# CC2530-CP2102-USB-V01-014.net
KiCad netlist of a schematic drawn in EAGLE
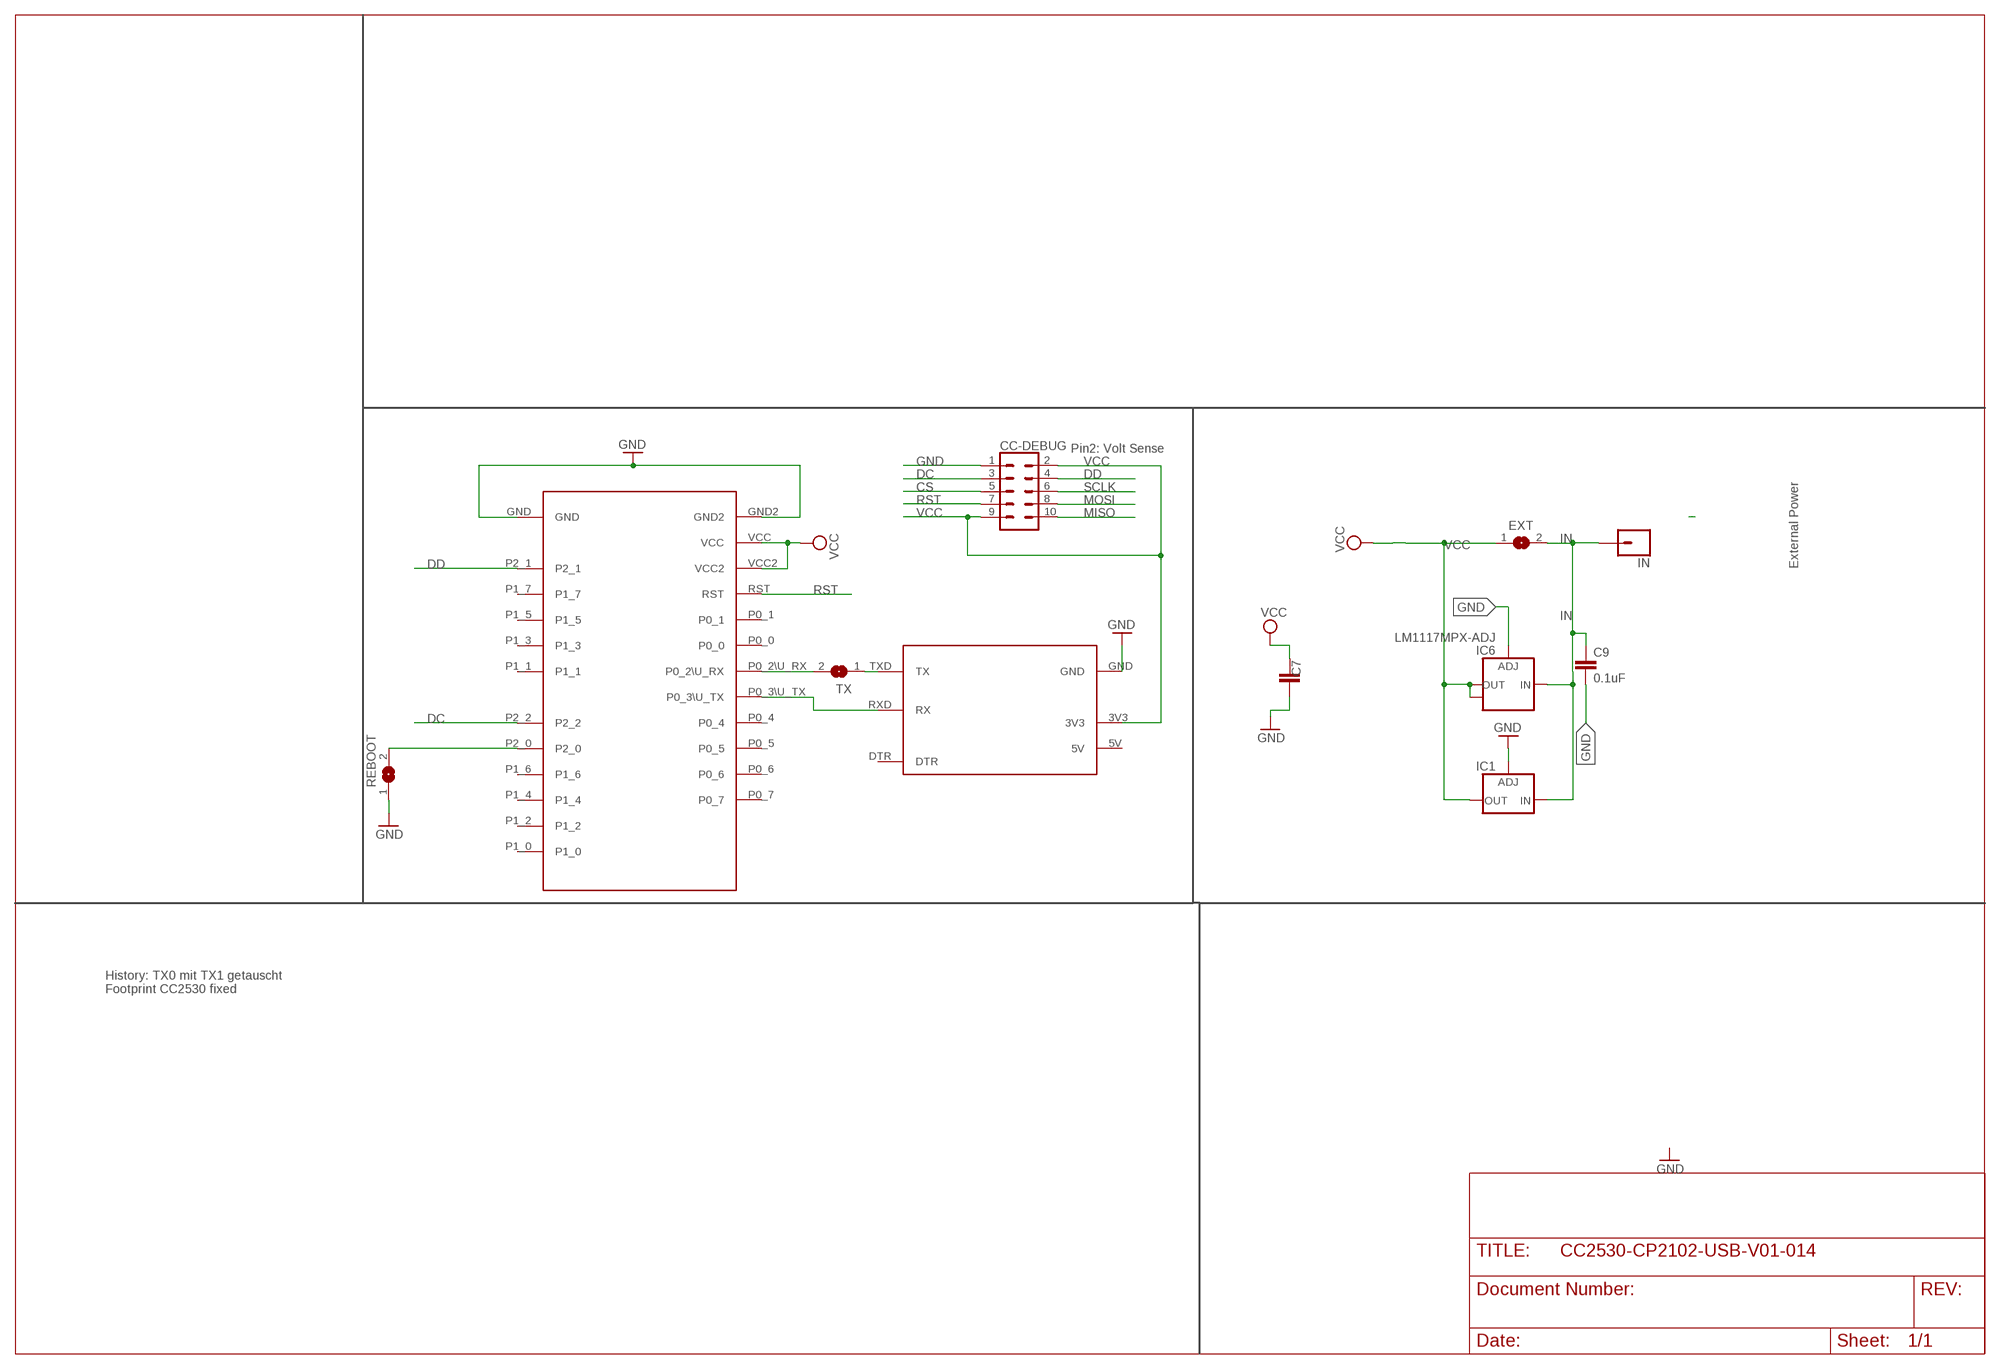
[diagram p0: schematic, sheet 1]

(export (version "E")
  (design (tool "Eeschema 10.0.6"))
  (components
    (comp (ref "C7")
      (value "C-EUC1812")
      (footprint "eagle-import:C1812")
      (libsource (lib "eagle-import") (part "C-EUC1812"))
    )
    (comp (ref "C9")
      (value "0.1uF")
      (footprint "eagle-import:C1206")
      (libsource (lib "eagle-import") (part "C-EUC1206"))
    )
    (comp (ref "CC-DEBUG")
      (value "CONN_05X2SHD_LOCK")
      (footprint "eagle-import:2X5-SHROUDED_LOCK")
      (libsource (lib "eagle-import") (part "CONN_05X2SHD_LOCK"))
    )
    (comp (ref "EXT") (value "SJ") (footprint "eagle-import:SJ") (libsource (lib "eagle-import") (part "SJ")))
    (comp (ref "IC1")
      (value "LD117ADT50TR")
      (footprint "eagle-import:DPACK")
      (libsource (lib "eagle-import") (part "LD117A?DT50TR"))
    )
    (comp (ref "IC6")
      (value "LM1117MPX-ADJ")
      (footprint "eagle-import:SOT223")
      (libsource (lib "eagle-import") (part "LM1117MPX-ADJ"))
    )
    (comp (ref "IN")
      (value "CONN_01")
      (footprint "eagle-import:1X01")
      (libsource (lib "eagle-import") (part "CONN_01"))
    )
    (comp (ref "REBOOT")
      (value "SJ")
      (footprint "eagle-import:SJ")
      (libsource (lib "eagle-import") (part "SJ"))
    )
    (comp (ref "TX") (value "SJ") (footprint "eagle-import:SJ") (libsource (lib "eagle-import") (part "SJ")))
    (comp (ref "U$1")
      (value "CP2101")
      (footprint "eagle-import:CP2101-BEAKOUT")
      (libsource (lib "eagle-import") (part "CP2101"))
    )
    (comp (ref "U$3")
      (value "CC2530_MODULE")
      (footprint "eagle-import:CC2530_DIL")
      (libsource (lib "eagle-import") (part "CC2530_MODULE"))
    )
  )
  (nets
    (net (code "1") (name "/5V") (class "Default")
      (node (ref "U$1") (pin "5V") (pinfunction "5V_5V") (pintype "power_in"))
    )
    (net (code "2") (name "/CS") (class "Default")
      (node (ref "CC-DEBUG") (pin "5") (pinfunction "5_5") (pintype "passive"))
    )
    (net (code "3") (name "/DC") (class "Default")
      (node (ref "CC-DEBUG") (pin "3") (pinfunction "3_3") (pintype "passive"))
      (node (ref "U$3") (pin "P2_2") (pinfunction "P2_2_P2_2") (pintype "bidirectional"))
    )
    (net (code "4") (name "/DD") (class "Default")
      (node (ref "CC-DEBUG") (pin "4") (pinfunction "4_4") (pintype "passive"))
      (node (ref "U$3") (pin "P2_1") (pinfunction "P2_1_P2_1") (pintype "bidirectional"))
    )
    (net (code "5") (name "/IN") (class "Default")
      (node (ref "C9") (pin "1") (pinfunction "1_1") (pintype "passive"))
      (node (ref "EXT") (pin "2") (pinfunction "2_2") (pintype "passive"))
      (node (ref "IC1") (pin "3") (pinfunction "IN_3") (pintype "input"))
      (node (ref "IC6") (pin "3") (pinfunction "IN_3") (pintype "input"))
      (node (ref "IN") (pin "1") (pinfunction "1_1") (pintype "passive"))
    )
    (net (code "6") (name "/MISO") (class "Default")
      (node (ref "CC-DEBUG") (pin "10") (pinfunction "10_10") (pintype "passive"))
    )
    (net (code "7") (name "/MOSI") (class "Default")
      (node (ref "CC-DEBUG") (pin "8") (pinfunction "8_8") (pintype "passive"))
    )
    (net (code "8") (name "/RST") (class "Default")
      (node (ref "CC-DEBUG") (pin "7") (pinfunction "7_7") (pintype "passive"))
      (node (ref "U$3") (pin "RST") (pinfunction "RST_RST") (pintype "bidirectional"))
    )
    (net (code "9") (name "/SCLK") (class "Default")
      (node (ref "CC-DEBUG") (pin "6") (pinfunction "6_6") (pintype "passive"))
    )
    (net (code "10") (name "GND") (class "Default")
      (node (ref "C7") (pin "1") (pinfunction "1_1") (pintype "passive"))
      (node (ref "C9") (pin "2") (pinfunction "2_2") (pintype "passive"))
      (node (ref "CC-DEBUG") (pin "1") (pinfunction "1_1") (pintype "passive"))
      (node (ref "IC1") (pin "1") (pinfunction "ADJ_1") (pintype "input"))
      (node (ref "IC6") (pin "1") (pinfunction "ADJ_1") (pintype "input"))
      (node (ref "REBOOT") (pin "1") (pinfunction "1_1") (pintype "passive"))
      (node (ref "U$1") (pin "GND") (pinfunction "GND_GND") (pintype "power_in"))
      (node (ref "U$3") (pin "GND") (pinfunction "GND_GND") (pintype "bidirectional"))
      (node (ref "U$3") (pin "GND2") (pinfunction "GND2_GND2") (pintype "bidirectional"))
    )
    (net (code "11") (name "Net-(REBOOT-Pad2)") (class "Default")
      (node (ref "REBOOT") (pin "2") (pinfunction "2_2") (pintype "passive"))
      (node (ref "U$3") (pin "P2_0") (pinfunction "P2_0_P2_0") (pintype "bidirectional"))
    )
    (net (code "12") (name "Net-(TX-Pad2)") (class "Default")
      (node (ref "TX") (pin "2") (pinfunction "2_2") (pintype "passive"))
      (node (ref "U$3") (pin "P0_2\\U_RX") (pinfunction "P0_2\\U_RX_P0_2\\U_RX") (pintype "bidirectional"))
    )
    (net (code "13") (name "Net-(U$1-RX)") (class "Default")
      (node (ref "U$1") (pin "RXD") (pinfunction "RX_RXD") (pintype "input"))
      (node (ref "U$3") (pin "P0_3\\U_TX") (pinfunction "P0_3\\U_TX_P0_3\\U_TX") (pintype "bidirectional"))
    )
    (net (code "14") (name "Net-(U$1-TX)") (class "Default")
      (node (ref "TX") (pin "1") (pinfunction "1_1") (pintype "passive"))
      (node (ref "U$1") (pin "TXD") (pinfunction "TX_TXD") (pintype "output"))
    )
    (net (code "15") (name "VCC") (class "Default")
      (node (ref "C7") (pin "2") (pinfunction "2_2") (pintype "passive"))
      (node (ref "CC-DEBUG") (pin "2") (pinfunction "2_2") (pintype "passive"))
      (node (ref "CC-DEBUG") (pin "9") (pinfunction "9_9") (pintype "passive"))
      (node (ref "EXT") (pin "1") (pinfunction "1_1") (pintype "passive"))
      (node (ref "IC1") (pin "4") (pinfunction "OUT_4") (pintype "passive"))
      (node (ref "IC6") (pin "2") (pinfunction "OUT_2") (pintype "passive"))
      (node (ref "IC6") (pin "TAB") (pinfunction "OUT1_TAB") (pintype "passive"))
      (node (ref "U$1") (pin "3V3") (pinfunction "3V3_3V3") (pintype "power_in"))
      (node (ref "U$3") (pin "VCC") (pinfunction "VCC_VCC") (pintype "bidirectional"))
      (node (ref "U$3") (pin "VCC2") (pinfunction "VCC2_VCC2") (pintype "bidirectional"))
    )
    (net (code "16") (name "unconnected-(U$1-PadDTR)") (class "Default")
      (node (ref "U$1") (pin "DTR") (pinfunction "DTR_DTR") (pintype "bidirectional"))
    )
    (net (code "17") (name "unconnected-(U$3-PadP0_0)") (class "Default")
      (node (ref "U$3") (pin "P0_0") (pinfunction "P0_0_P0_0") (pintype "bidirectional"))
    )
    (net (code "18") (name "unconnected-(U$3-PadP0_1)") (class "Default")
      (node (ref "U$3") (pin "P0_1") (pinfunction "P0_1_P0_1") (pintype "bidirectional"))
    )
    (net (code "19") (name "unconnected-(U$3-PadP0_4)") (class "Default")
      (node (ref "U$3") (pin "P0_4") (pinfunction "P0_4_P0_4") (pintype "bidirectional"))
    )
    (net (code "20") (name "unconnected-(U$3-PadP0_5)") (class "Default")
      (node (ref "U$3") (pin "P0_5") (pinfunction "P0_5_P0_5") (pintype "bidirectional"))
    )
    (net (code "21") (name "unconnected-(U$3-PadP0_6)") (class "Default")
      (node (ref "U$3") (pin "P0_6") (pinfunction "P0_6_P0_6") (pintype "bidirectional"))
    )
    (net (code "22") (name "unconnected-(U$3-PadP0_7)") (class "Default")
      (node (ref "U$3") (pin "P0_7") (pinfunction "P0_7_P0_7") (pintype "bidirectional"))
    )
    (net (code "23") (name "unconnected-(U$3-PadP1_0)") (class "Default")
      (node (ref "U$3") (pin "P1_0") (pinfunction "P1_0_P1_0") (pintype "bidirectional"))
    )
    (net (code "24") (name "unconnected-(U$3-PadP1_1)") (class "Default")
      (node (ref "U$3") (pin "P1_1") (pinfunction "P1_1_P1_1") (pintype "bidirectional"))
    )
    (net (code "25") (name "unconnected-(U$3-PadP1_2)") (class "Default")
      (node (ref "U$3") (pin "P1_2") (pinfunction "P1_2_P1_2") (pintype "bidirectional"))
    )
    (net (code "26") (name "unconnected-(U$3-PadP1_3)") (class "Default")
      (node (ref "U$3") (pin "P1_3") (pinfunction "P1_3_P1_3") (pintype "bidirectional"))
    )
    (net (code "27") (name "unconnected-(U$3-PadP1_4)") (class "Default")
      (node (ref "U$3") (pin "P1_4") (pinfunction "P1_4_P1_4") (pintype "bidirectional"))
    )
    (net (code "28") (name "unconnected-(U$3-PadP1_5)") (class "Default")
      (node (ref "U$3") (pin "P1_5") (pinfunction "P1_5_P1_5") (pintype "bidirectional"))
    )
    (net (code "29") (name "unconnected-(U$3-PadP1_6)") (class "Default")
      (node (ref "U$3") (pin "P1_6") (pinfunction "P1_6_P1_6") (pintype "bidirectional"))
    )
    (net (code "30") (name "unconnected-(U$3-PadP1_7)") (class "Default")
      (node (ref "U$3") (pin "P1_7") (pinfunction "P1_7_P1_7") (pintype "bidirectional"))
    )
  )
)
